# INA240_Breakout.net
KiCad netlist of a schematic drawn in Altium Designer
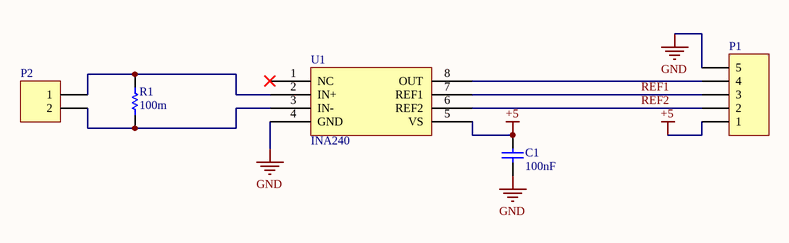
[diagram p0: INA240_Breakout.SchDoc]

(export (version "E")
  (design (tool "Eeschema 10.0.6"))
  (components
    (comp (ref "C1")
      (value "100nF")
      (footprint "0805 - Capacitor")
      (description "Nonpolarized Capacitor")
      (fields
        (field (name "MANUFACTURER") "Yageo")
        (field (name "MANUFACTURER PART NUMBER") "CC0805KRX7R9BB104")
      )
      (libsource (lib "General") (part "Capacitor - Nonpolarized"))
    )
    (comp (ref "P1")
      (value "1x5 Header")
      (footprint "HDR1X5")
      (description "1x5 Pin Header")
      (libsource (lib "GeneralConnectors") (part "1x5 Header"))
    )
    (comp (ref "P2")
      (value "1x2 Header")
      (footprint "HDR1X2")
      (description "1x2 Pin Header")
      (libsource (lib "GeneralConnectors") (part "1x2 Header"))
    )
    (comp (ref "R1")
      (value "100m")
      (footprint "0603 - Resistor")
      (description "Resistor")
      (fields (field (name "MANUFACTURER PART NUMBER") "73L3R10J") (field (name "MANUFACTURER") "CTS"))
      (libsource (lib "General") (part "Resistor"))
    )
    (comp (ref "U1")
      (value "INA240")
      (footprint "INA240")
      (description "-4V to 80V Current Sense Amplifier")
      (fields
        (field (name "MANUFACTURER") "Texas Instruments")
        (field (name "MANUFACTURER PART NUMBER") "INA240A2DR")
      )
      (libsource (lib "GeneralComponents") (part "INA240"))
    )
  )
  (nets
    (net (code "1") (name "+5") (class "Default")
      (node (ref "C1") (pin "2") (pinfunction "2_2") (pintype "passive"))
      (node (ref "P1") (pin "1") (pinfunction "1_1") (pintype "passive"))
      (node (ref "U1") (pin "5") (pinfunction "VS_5") (pintype "power_in"))
    )
    (net (code "2") (name "/REF1") (class "Default")
      (node (ref "P1") (pin "3") (pinfunction "3_3") (pintype "passive"))
      (node (ref "U1") (pin "7") (pinfunction "REF1_7") (pintype "passive"))
    )
    (net (code "3") (name "/REF2") (class "Default")
      (node (ref "P1") (pin "2") (pinfunction "2_2") (pintype "passive"))
      (node (ref "U1") (pin "6") (pinfunction "REF2_6") (pintype "passive"))
    )
    (net (code "4") (name "GND") (class "Default")
      (node (ref "C1") (pin "1") (pinfunction "1_1") (pintype "passive"))
      (node (ref "P1") (pin "5") (pinfunction "5_5") (pintype "passive"))
      (node (ref "U1") (pin "4") (pinfunction "GND_4") (pintype "power_in"))
    )
    (net (code "5") (name "Net-(U1-IN+)") (class "Default")
      (node (ref "P2") (pin "1") (pinfunction "1_1") (pintype "passive"))
      (node (ref "R1") (pin "1") (pinfunction "1_1") (pintype "passive"))
      (node (ref "U1") (pin "2") (pinfunction "IN+_2") (pintype "passive"))
    )
    (net (code "6") (name "Net-(U1-IN-)") (class "Default")
      (node (ref "P2") (pin "2") (pinfunction "2_2") (pintype "passive"))
      (node (ref "R1") (pin "2") (pinfunction "2_2") (pintype "passive"))
      (node (ref "U1") (pin "3") (pinfunction "IN-_3") (pintype "passive"))
    )
    (net (code "7") (name "Net-(U1-OUT)") (class "Default")
      (node (ref "P1") (pin "4") (pinfunction "4_4") (pintype "passive"))
      (node (ref "U1") (pin "8") (pinfunction "OUT_8") (pintype "passive"))
    )
    (net (code "8") (name "unconnected-(U1-NC-Pad1)") (class "Default")
      (node (ref "U1") (pin "1") (pinfunction "NC_1") (pintype "passive+no_connect"))
    )
  )
)
